# ZumoAdapterboardv2.net
KiCad netlist of a schematic drawn in EAGLE
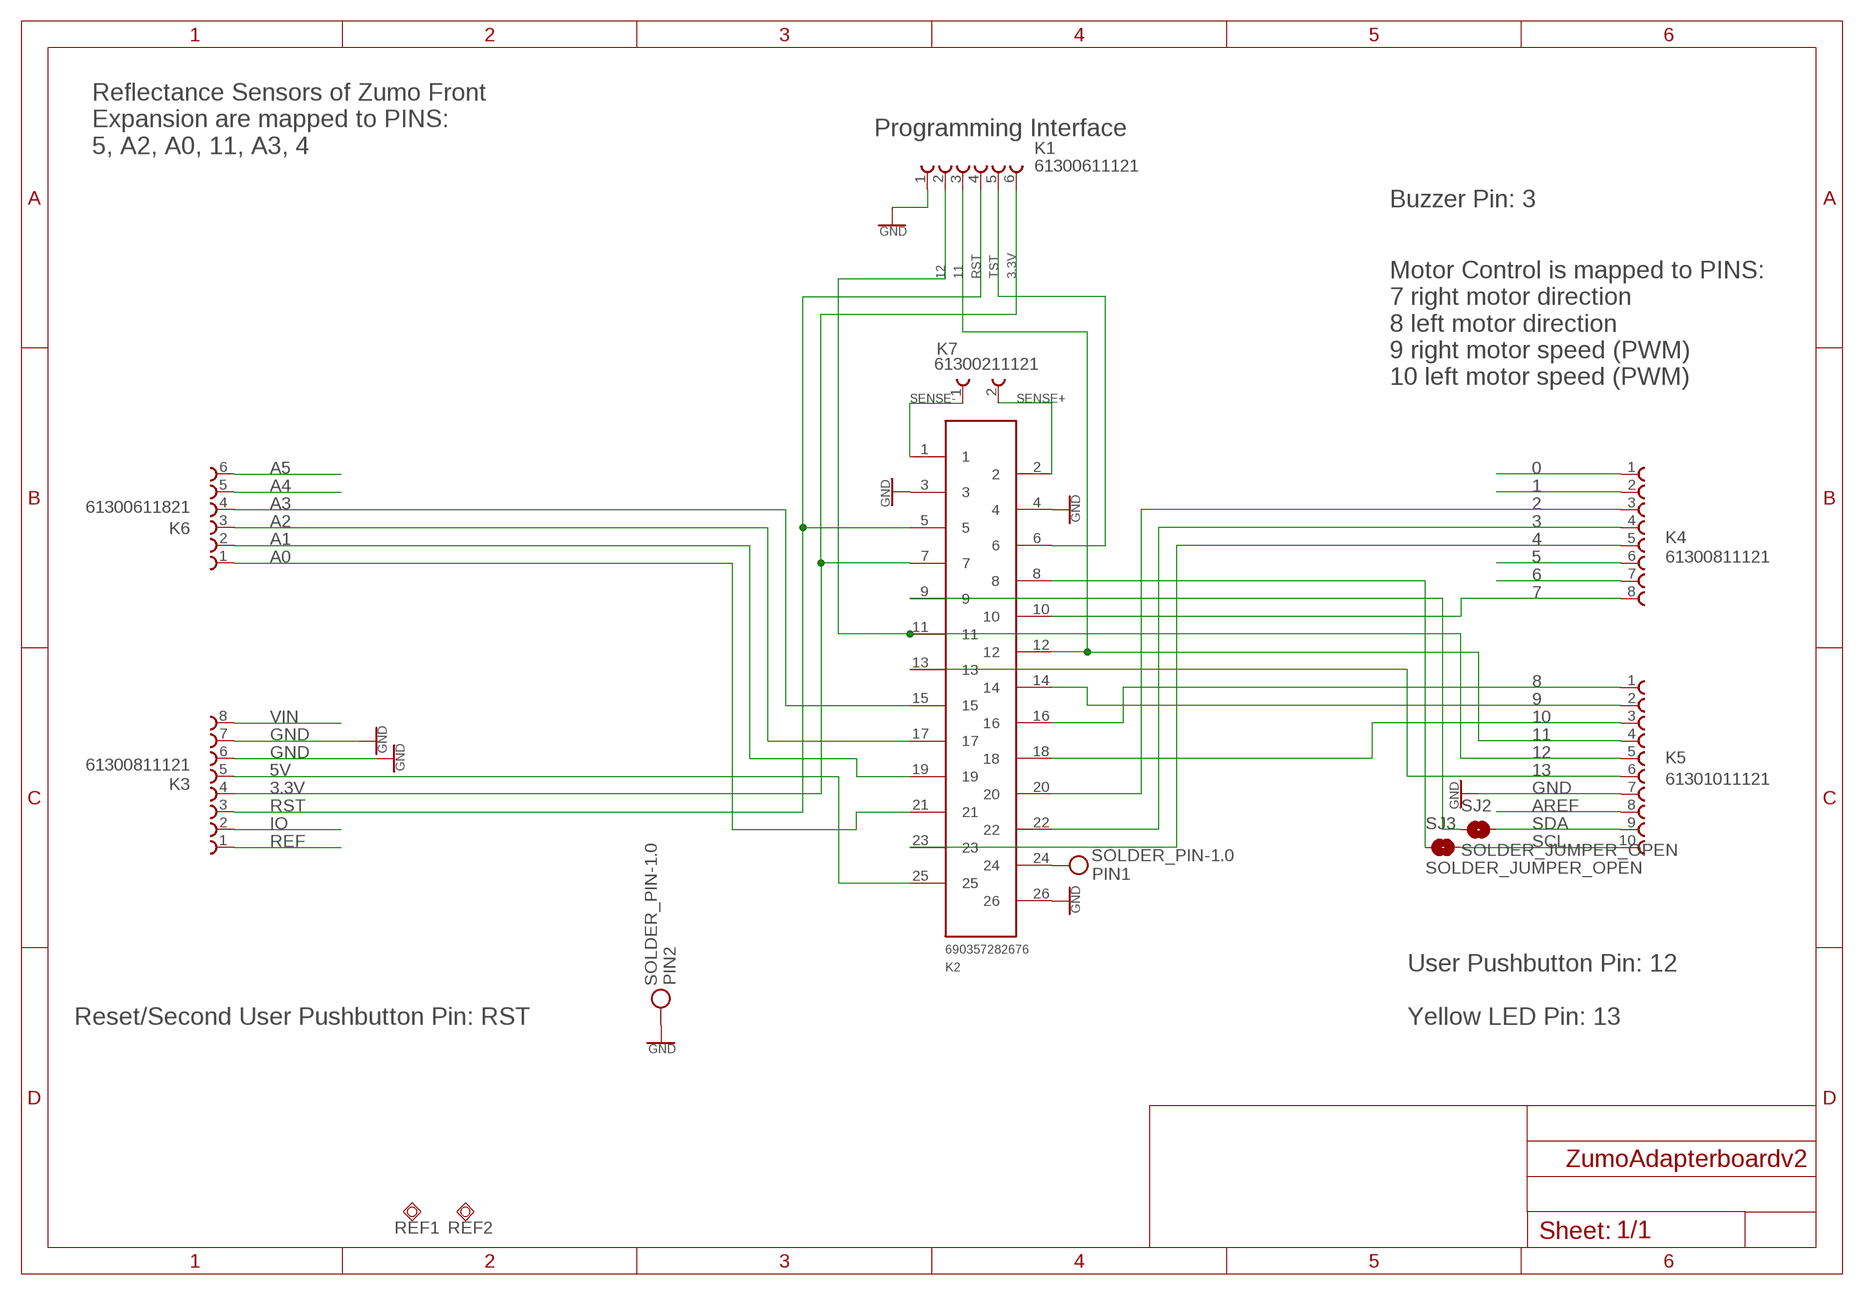
[diagram p0: schematic, sheet 1]

(export (version "E")
  (design (tool "Eeschema 10.0.6"))
  (components
    (comp (ref "K1")
      (value "61300611121")
      (footprint "eagle-import:61300611121")
      (libsource (lib "eagle-import") (part "61300611121"))
    )
    (comp (ref "K2")
      (value "690357282676")
      (footprint "eagle-import:690357282676")
      (libsource (lib "eagle-import") (part "690357282676"))
    )
    (comp (ref "K3")
      (value "61300811121")
      (footprint "eagle-import:61300811121")
      (libsource (lib "eagle-import") (part "61300811121"))
    )
    (comp (ref "K4")
      (value "61300811121")
      (footprint "eagle-import:61300811121")
      (libsource (lib "eagle-import") (part "61300811121"))
    )
    (comp (ref "K5")
      (value "61301011121")
      (footprint "eagle-import:61301011121")
      (libsource (lib "eagle-import") (part "61301011121"))
    )
    (comp (ref "K6")
      (value "61300611821")
      (footprint "eagle-import:61300611821")
      (libsource (lib "eagle-import") (part "61300611821"))
    )
    (comp (ref "K7")
      (value "61300211121")
      (footprint "eagle-import:61300211121")
      (libsource (lib "eagle-import") (part "61300211121"))
    )
    (comp (ref "PIN1")
      (value "SOLDER_PIN-1.0")
      (footprint "eagle-import:SOLDER_PIN_1.0")
      (libsource (lib "eagle-import") (part "SOLDER_PIN-1.0"))
    )
    (comp (ref "PIN2")
      (value "SOLDER_PIN-1.0")
      (footprint "eagle-import:SOLDER_PIN_1.0")
      (libsource (lib "eagle-import") (part "SOLDER_PIN-1.0"))
    )
    (comp (ref "REF1")
      (value "PCB-REF-1.27")
      (footprint "eagle-import:PCB-REF")
      (libsource (lib "eagle-import") (part "PCB-REF-1.27"))
    )
    (comp (ref "REF2")
      (value "PCB-REF-1.27")
      (footprint "eagle-import:PCB-REF")
      (libsource (lib "eagle-import") (part "PCB-REF-1.27"))
    )
    (comp (ref "SJ2")
      (value "SOLDER_JUMPER_OPEN")
      (footprint "eagle-import:SJ-O")
      (libsource (lib "eagle-import") (part "SOLDER_JUMPER_OPEN"))
    )
    (comp (ref "SJ3")
      (value "SOLDER_JUMPER_OPEN")
      (footprint "eagle-import:SJ-O")
      (libsource (lib "eagle-import") (part "SOLDER_JUMPER_OPEN"))
    )
  )
  (nets
    (net (code "1") (name "/0") (class "Default")
      (node (ref "K4") (pin "1") (pinfunction "1_1") (pintype "passive"))
    )
    (net (code "2") (name "/1") (class "Default")
      (node (ref "K4") (pin "2") (pinfunction "2_2") (pintype "passive"))
    )
    (net (code "3") (name "/2") (class "Default")
      (node (ref "K2") (pin "20") (pinfunction "20_20") (pintype "passive"))
      (node (ref "K4") (pin "3") (pinfunction "3_3") (pintype "passive"))
    )
    (net (code "4") (name "/3") (class "Default")
      (node (ref "K2") (pin "22") (pinfunction "22_22") (pintype "passive"))
      (node (ref "K4") (pin "4") (pinfunction "4_4") (pintype "passive"))
    )
    (net (code "5") (name "/3.3V") (class "Default")
      (node (ref "K1") (pin "6") (pinfunction "6_6") (pintype "passive"))
      (node (ref "K2") (pin "7") (pinfunction "7_7") (pintype "passive"))
      (node (ref "K3") (pin "4") (pinfunction "4_4") (pintype "passive"))
    )
    (net (code "6") (name "/4") (class "Default")
      (node (ref "K2") (pin "23") (pinfunction "23_23") (pintype "passive"))
      (node (ref "K4") (pin "5") (pinfunction "5_5") (pintype "passive"))
    )
    (net (code "7") (name "/5") (class "Default")
      (node (ref "K4") (pin "6") (pinfunction "6_6") (pintype "passive"))
    )
    (net (code "8") (name "/5V") (class "Default")
      (node (ref "K2") (pin "25") (pinfunction "25_25") (pintype "passive"))
      (node (ref "K3") (pin "5") (pinfunction "5_5") (pintype "passive"))
    )
    (net (code "9") (name "/6") (class "Default")
      (node (ref "K4") (pin "7") (pinfunction "7_7") (pintype "passive"))
    )
    (net (code "10") (name "/7") (class "Default")
      (node (ref "K2") (pin "10") (pinfunction "10_10") (pintype "passive"))
      (node (ref "K4") (pin "8") (pinfunction "8_8") (pintype "passive"))
    )
    (net (code "11") (name "/8") (class "Default")
      (node (ref "K2") (pin "16") (pinfunction "16_16") (pintype "passive"))
      (node (ref "K5") (pin "1") (pinfunction "1_1") (pintype "passive"))
    )
    (net (code "12") (name "/9") (class "Default")
      (node (ref "K2") (pin "14") (pinfunction "14_14") (pintype "passive"))
      (node (ref "K5") (pin "2") (pinfunction "2_2") (pintype "passive"))
    )
    (net (code "13") (name "/10") (class "Default")
      (node (ref "K2") (pin "18") (pinfunction "18_18") (pintype "passive"))
      (node (ref "K5") (pin "3") (pinfunction "3_3") (pintype "passive"))
    )
    (net (code "14") (name "/11") (class "Default")
      (node (ref "K1") (pin "3") (pinfunction "3_3") (pintype "passive"))
      (node (ref "K2") (pin "12") (pinfunction "12_12") (pintype "passive"))
      (node (ref "K5") (pin "4") (pinfunction "4_4") (pintype "passive"))
    )
    (net (code "15") (name "/12") (class "Default")
      (node (ref "K1") (pin "2") (pinfunction "2_2") (pintype "passive"))
      (node (ref "K2") (pin "11") (pinfunction "11_11") (pintype "passive"))
      (node (ref "K5") (pin "5") (pinfunction "5_5") (pintype "passive"))
    )
    (net (code "16") (name "/13") (class "Default")
      (node (ref "K2") (pin "13") (pinfunction "13_13") (pintype "passive"))
      (node (ref "K5") (pin "6") (pinfunction "6_6") (pintype "passive"))
    )
    (net (code "17") (name "/A0") (class "Default")
      (node (ref "K2") (pin "21") (pinfunction "21_21") (pintype "passive"))
      (node (ref "K6") (pin "1") (pinfunction "1_1") (pintype "passive"))
    )
    (net (code "18") (name "/A1") (class "Default")
      (node (ref "K2") (pin "19") (pinfunction "19_19") (pintype "passive"))
      (node (ref "K6") (pin "2") (pinfunction "2_2") (pintype "passive"))
    )
    (net (code "19") (name "/A2") (class "Default")
      (node (ref "K2") (pin "17") (pinfunction "17_17") (pintype "passive"))
      (node (ref "K6") (pin "3") (pinfunction "3_3") (pintype "passive"))
    )
    (net (code "20") (name "/A3") (class "Default")
      (node (ref "K2") (pin "15") (pinfunction "15_15") (pintype "passive"))
      (node (ref "K6") (pin "4") (pinfunction "4_4") (pintype "passive"))
    )
    (net (code "21") (name "/A4") (class "Default")
      (node (ref "K6") (pin "5") (pinfunction "5_5") (pintype "passive"))
    )
    (net (code "22") (name "/A5") (class "Default")
      (node (ref "K6") (pin "6") (pinfunction "6_6") (pintype "passive"))
    )
    (net (code "23") (name "/AREF") (class "Default")
      (node (ref "K5") (pin "8") (pinfunction "8_8") (pintype "passive"))
    )
    (net (code "24") (name "/IO") (class "Default")
      (node (ref "K3") (pin "2") (pinfunction "2_2") (pintype "passive"))
    )
    (net (code "25") (name "/REF") (class "Default")
      (node (ref "K3") (pin "1") (pinfunction "1_1") (pintype "passive"))
    )
    (net (code "26") (name "/RST") (class "Default")
      (node (ref "K1") (pin "4") (pinfunction "4_4") (pintype "passive"))
      (node (ref "K2") (pin "5") (pinfunction "5_5") (pintype "passive"))
      (node (ref "K3") (pin "3") (pinfunction "3_3") (pintype "passive"))
    )
    (net (code "27") (name "/SCL") (class "Default")
      (node (ref "K5") (pin "10") (pinfunction "10_10") (pintype "passive"))
      (node (ref "SJ3") (pin "2") (pinfunction "2_2") (pintype "passive"))
    )
    (net (code "28") (name "/SDA") (class "Default")
      (node (ref "K5") (pin "9") (pinfunction "9_9") (pintype "passive"))
      (node (ref "SJ2") (pin "2") (pinfunction "2_2") (pintype "passive"))
    )
    (net (code "29") (name "/SENSE+") (class "Default")
      (node (ref "K2") (pin "2") (pinfunction "2_2") (pintype "passive"))
      (node (ref "K7") (pin "2") (pinfunction "2_2") (pintype "passive"))
    )
    (net (code "30") (name "/SENSE-") (class "Default")
      (node (ref "K2") (pin "1") (pinfunction "1_1") (pintype "passive"))
      (node (ref "K7") (pin "1") (pinfunction "1_1") (pintype "passive"))
    )
    (net (code "31") (name "/TST") (class "Default")
      (node (ref "K1") (pin "5") (pinfunction "5_5") (pintype "passive"))
      (node (ref "K2") (pin "6") (pinfunction "6_6") (pintype "passive"))
    )
    (net (code "32") (name "/VIN") (class "Default")
      (node (ref "K3") (pin "8") (pinfunction "8_8") (pintype "passive"))
    )
    (net (code "33") (name "GND") (class "Default")
      (node (ref "K1") (pin "1") (pinfunction "1_1") (pintype "passive"))
      (node (ref "K2") (pin "26") (pinfunction "26_26") (pintype "passive"))
      (node (ref "K2") (pin "3") (pinfunction "3_3") (pintype "passive"))
      (node (ref "K2") (pin "4") (pinfunction "4_4") (pintype "passive"))
      (node (ref "K3") (pin "6") (pinfunction "6_6") (pintype "passive"))
      (node (ref "K3") (pin "7") (pinfunction "7_7") (pintype "passive"))
      (node (ref "K5") (pin "7") (pinfunction "7_7") (pintype "passive"))
      (node (ref "PIN2") (pin "_") (pinfunction "PIN__") (pintype "passive"))
    )
    (net (code "34") (name "Net-(K2-Pad8)") (class "Default")
      (node (ref "K2") (pin "8") (pinfunction "8_8") (pintype "passive"))
      (node (ref "SJ3") (pin "1") (pinfunction "1_1") (pintype "passive"))
    )
    (net (code "35") (name "Net-(K2-Pad9)") (class "Default")
      (node (ref "K2") (pin "9") (pinfunction "9_9") (pintype "passive"))
      (node (ref "SJ2") (pin "1") (pinfunction "1_1") (pintype "passive"))
    )
    (net (code "36") (name "Net-(PIN1-PIN)") (class "Default")
      (node (ref "K2") (pin "24") (pinfunction "24_24") (pintype "passive"))
      (node (ref "PIN1") (pin "_") (pinfunction "PIN__") (pintype "passive"))
    )
    (net (code "37") (name "unconnected-(REF1-PP-Pad0)") (class "Default")
      (node (ref "REF1") (pin "0") (pinfunction "PP_0") (pintype "no_connect"))
    )
    (net (code "38") (name "unconnected-(REF2-PP-Pad0)") (class "Default")
      (node (ref "REF2") (pin "0") (pinfunction "PP_0") (pintype "no_connect"))
    )
  )
)
